# MODULO_CNY70.net
KiCad netlist of a schematic drawn in EAGLE
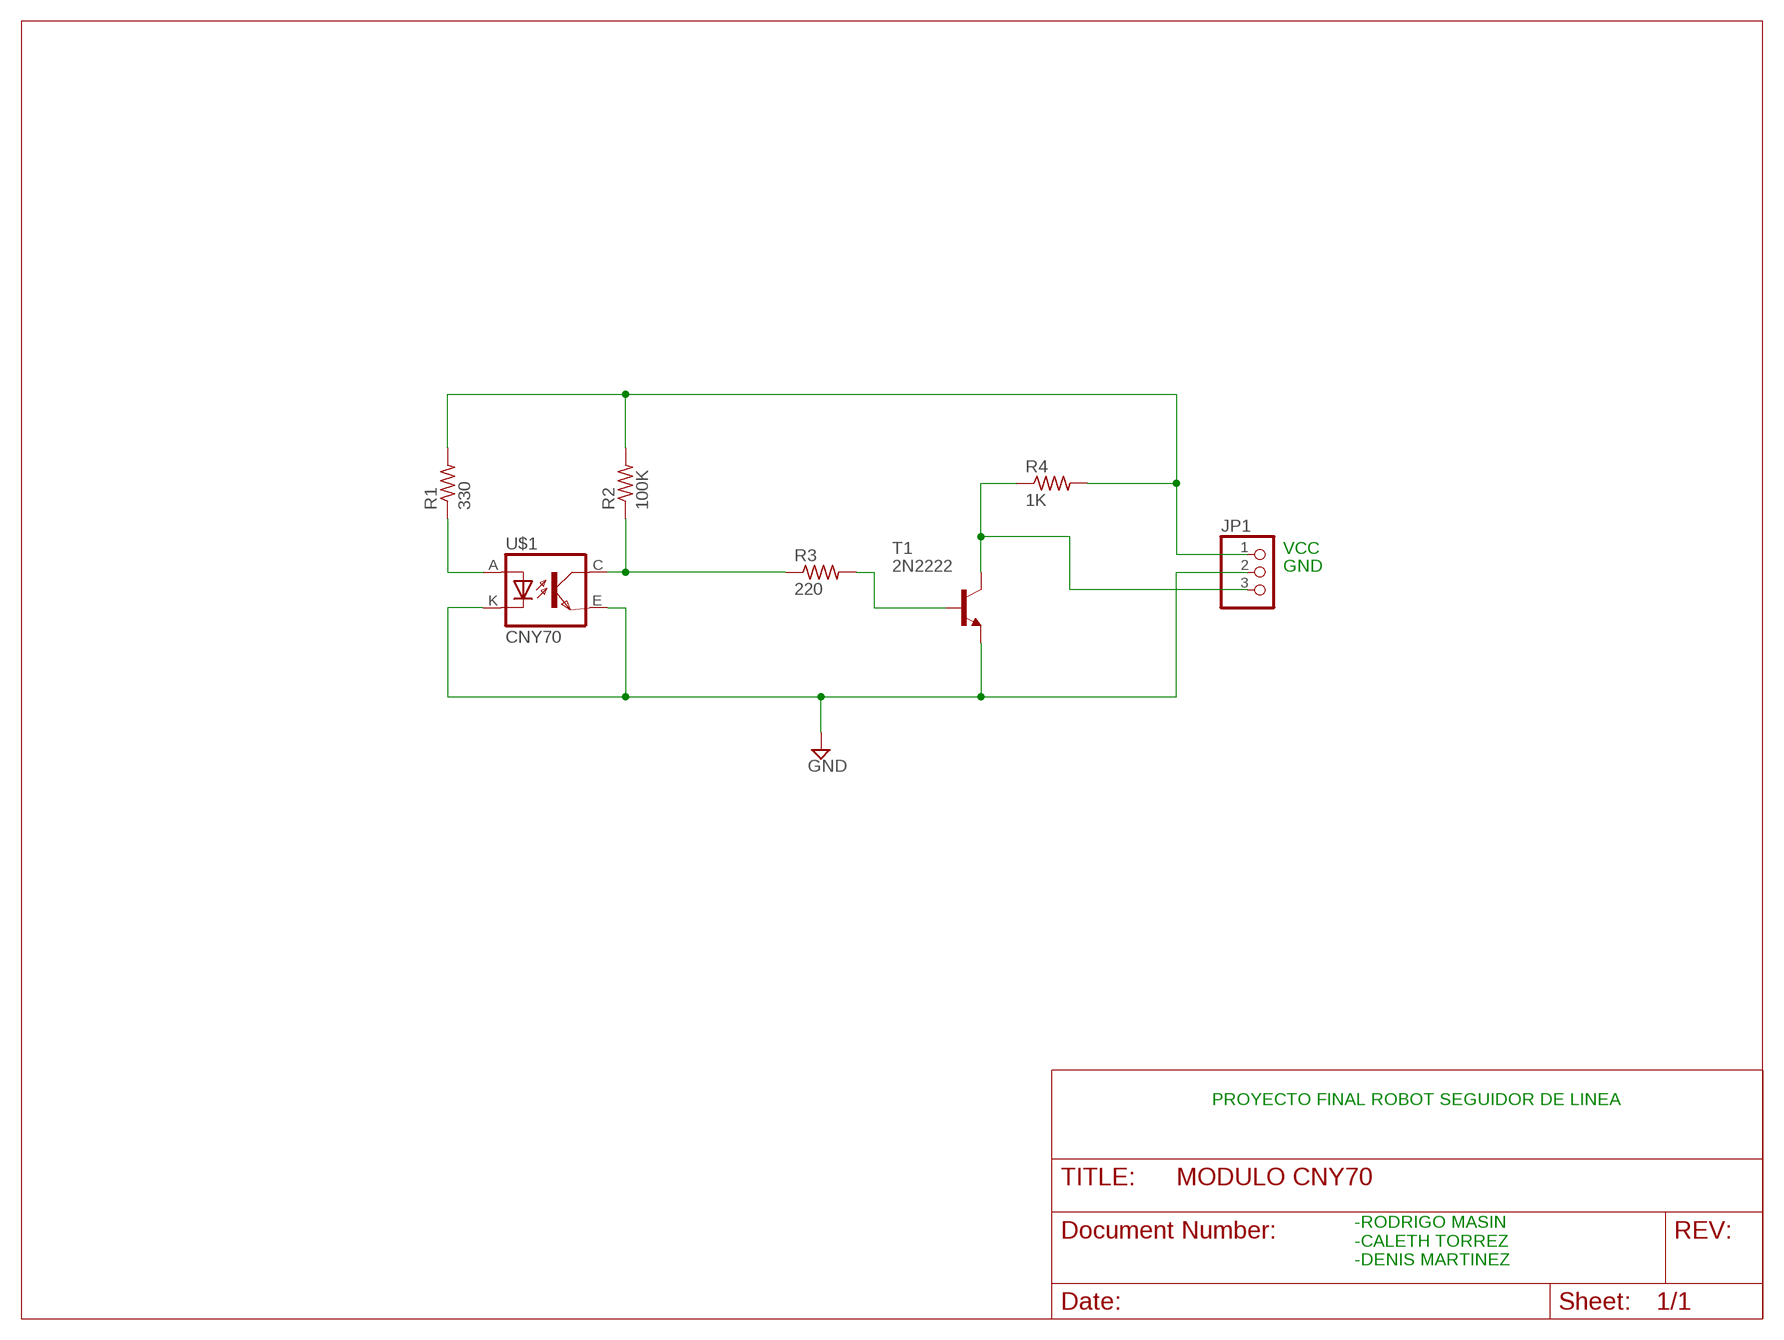
[diagram p0: schematic, sheet 1]

(export (version "E")
  (design (tool "Eeschema 10.0.6"))
  (components
    (comp (ref "JP1")
      (value "PINHD-1X3")
      (footprint "eagle-import:1X03")
      (libsource (lib "eagle-import") (part "PINHD-1X3"))
    )
    (comp (ref "R1")
      (value "330")
      (footprint "eagle-import:0207_7")
      (libsource (lib "eagle-import") (part "R-US_0207/7"))
    )
    (comp (ref "R2")
      (value "100K")
      (footprint "eagle-import:0207_7")
      (libsource (lib "eagle-import") (part "R-US_0207/7"))
    )
    (comp (ref "R3")
      (value "220")
      (footprint "eagle-import:0207_7")
      (libsource (lib "eagle-import") (part "R-US_0207/7"))
    )
    (comp (ref "R4")
      (value "1K")
      (footprint "eagle-import:0207_7")
      (libsource (lib "eagle-import") (part "R-US_0207/7"))
    )
    (comp (ref "T1")
      (value "2N2222")
      (footprint "eagle-import:TO18")
      (libsource (lib "eagle-import") (part "2N2222"))
    )
    (comp (ref "U$1")
      (value "CNY70")
      (footprint "eagle-import:4")
      (libsource (lib "eagle-import") (part "CNY70"))
    )
  )
  (nets
    (net (code "1") (name "GND") (class "Default")
      (node (ref "JP1") (pin "2") (pinfunction "2_2") (pintype "passive"))
      (node (ref "T1") (pin "1") (pinfunction "E_1") (pintype "passive"))
      (node (ref "U$1") (pin "E") (pinfunction "EMI_E") (pintype "passive"))
      (node (ref "U$1") (pin "K") (pinfunction "C_K") (pintype "passive"))
    )
    (net (code "2") (name "Net-(JP1-Pad1)") (class "Default")
      (node (ref "JP1") (pin "1") (pinfunction "1_1") (pintype "passive"))
      (node (ref "R1") (pin "2") (pinfunction "2_2") (pintype "passive"))
      (node (ref "R2") (pin "2") (pinfunction "2_2") (pintype "passive"))
      (node (ref "R4") (pin "2") (pinfunction "2_2") (pintype "passive"))
    )
    (net (code "3") (name "Net-(R1-Pad1)") (class "Default")
      (node (ref "R1") (pin "1") (pinfunction "1_1") (pintype "passive"))
      (node (ref "U$1") (pin "A") (pinfunction "A_A") (pintype "passive"))
    )
    (net (code "4") (name "Net-(T1-B)") (class "Default")
      (node (ref "R3") (pin "2") (pinfunction "2_2") (pintype "passive"))
      (node (ref "T1") (pin "2") (pinfunction "B_2") (pintype "passive"))
    )
    (net (code "5") (name "Net-(T1-C)") (class "Default")
      (node (ref "JP1") (pin "3") (pinfunction "3_3") (pintype "passive"))
      (node (ref "R4") (pin "1") (pinfunction "1_1") (pintype "passive"))
      (node (ref "T1") (pin "3") (pinfunction "C_3") (pintype "passive"))
    )
    (net (code "6") (name "Net-(U$1-COL)") (class "Default")
      (node (ref "R2") (pin "1") (pinfunction "1_1") (pintype "passive"))
      (node (ref "R3") (pin "1") (pinfunction "1_1") (pintype "passive"))
      (node (ref "U$1") (pin "C") (pinfunction "COL_C") (pintype "passive"))
    )
  )
)
